# xlr_ingang.net
KiCad netlist of a schematic drawn in Altium Designer
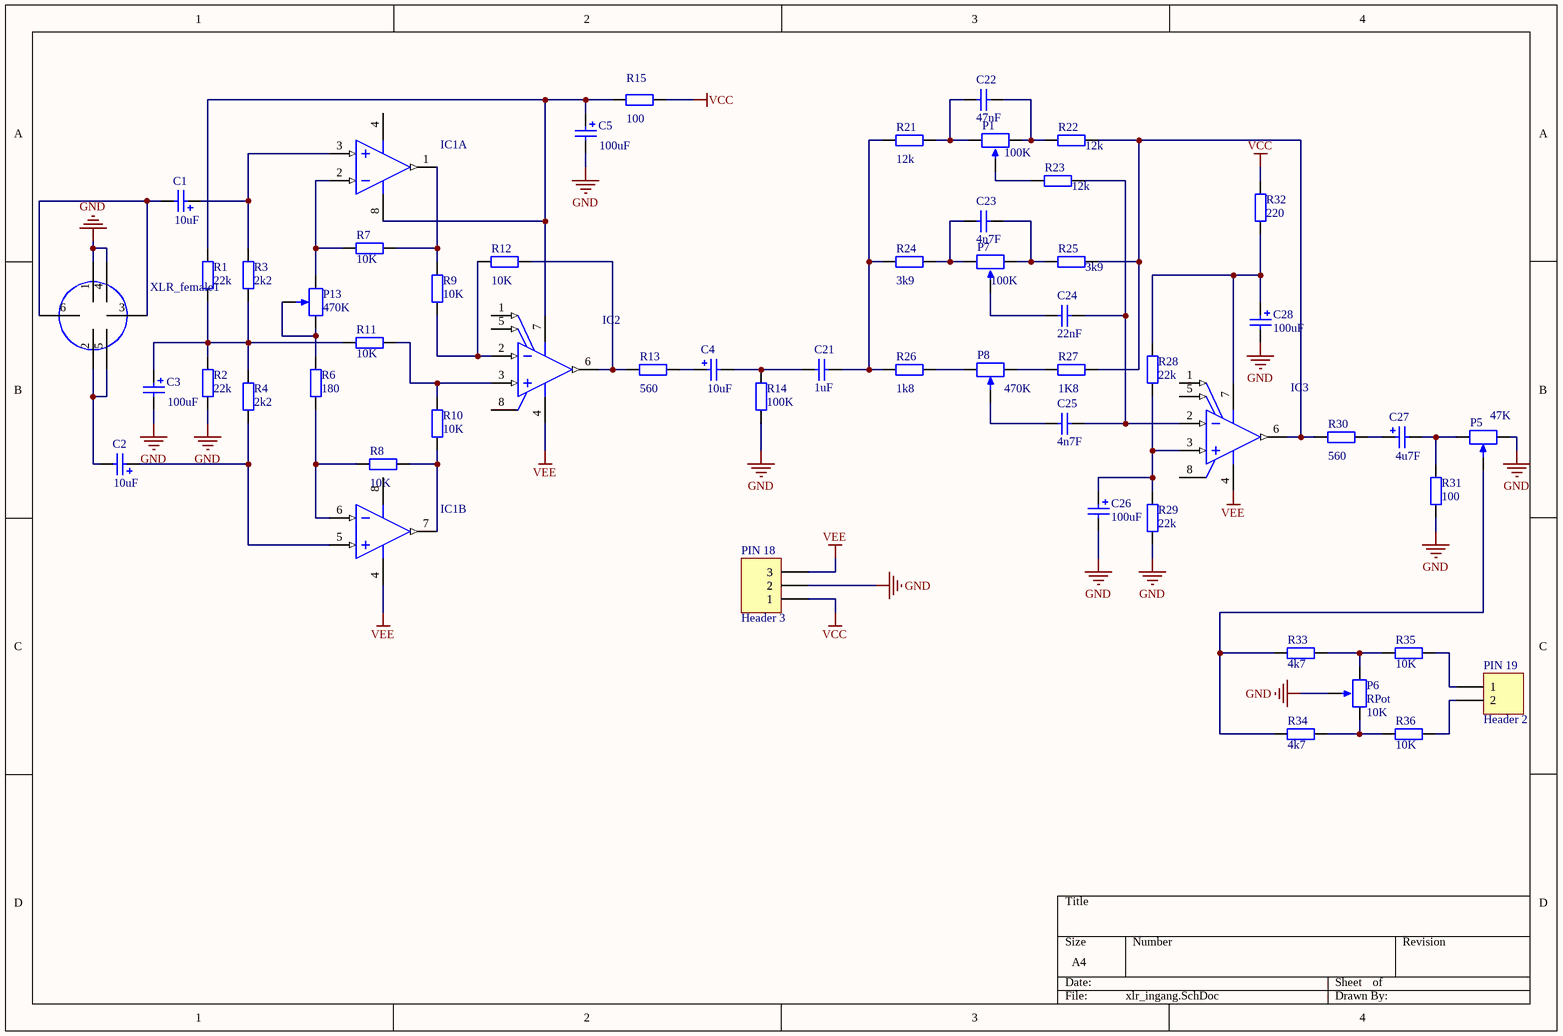
[diagram p0: xlr_ingang.SchDoc]

(export (version "E")
  (design (tool "Eeschema 10.0.6"))
  (components
    (comp (ref "C1")
      (value "10uF")
      (footprint "Capacitor 10uF")
      (description "Polarized Capacitor (Axial)")
      (fields (field (name "Comment") "Cap Pol2") (field (name "PUBLISHER") "Altium Limited"))
      (libsource (lib "Miscellaneous Devices") (part "Cap Pol2"))
    )
    (comp (ref "C2")
      (value "10uF")
      (footprint "Capacitor 10uF")
      (description "Polarized Capacitor (Axial)")
      (fields (field (name "Comment") "Cap Pol2") (field (name "PUBLISHER") "Altium Limited"))
      (libsource (lib "Miscellaneous Devices") (part "Cap Pol2"))
    )
    (comp (ref "C3")
      (value "100uF")
      (footprint "Capacitor 100uF")
      (description "Polarized Capacitor (Axial)")
      (fields (field (name "Comment") "Cap Pol2") (field (name "PUBLISHER") "Altium Limited"))
      (libsource (lib "Miscellaneous Devices") (part "Cap Pol2"))
    )
    (comp (ref "C4")
      (value "10uF")
      (footprint "Capacitor 10uF")
      (description "Polarized Capacitor (Axial)")
      (fields (field (name "Comment") "Cap Pol2") (field (name "PUBLISHER") "Altium Limited"))
      (libsource (lib "Miscellaneous Devices") (part "Cap Pol2"))
    )
    (comp (ref "C5")
      (value "100uF")
      (footprint "Capacitor 100uF")
      (description "Polarized Capacitor (Axial)")
      (fields (field (name "Comment") "Cap Pol2") (field (name "PUBLISHER") "Altium Limited"))
      (libsource (lib "Miscellaneous Devices") (part "Cap Pol2"))
    )
    (comp (ref "C21")
      (value "1uF")
      (footprint "Capacitor 1uF")
      (description "Capacitor")
      (fields (field (name "Comment") "Cap") (field (name "PUBLISHER") "Altium Limited"))
      (libsource (lib "Autio_Mixer") (part "Cap"))
    )
    (comp (ref "C22")
      (value "47nF")
      (footprint "Capacitor 22nF, 47nF, 100nF")
      (description "Capacitor")
      (fields (field (name "Comment") "Cap") (field (name "PUBLISHER") "Altium Limited"))
      (libsource (lib "Autio_Mixer") (part "Cap"))
    )
    (comp (ref "C23")
      (value "4n7F")
      (footprint "Capacitor 22nF, 47nF, 100nF")
      (description "Capacitor")
      (fields (field (name "Comment") "Cap") (field (name "PUBLISHER") "Altium Limited"))
      (libsource (lib "Autio_Mixer") (part "Cap"))
    )
    (comp (ref "C24")
      (value "22nF")
      (footprint "Capacitor 22nF, 47nF, 100nF")
      (description "Capacitor")
      (fields (field (name "Comment") "Cap") (field (name "PUBLISHER") "Altium Limited"))
      (libsource (lib "Autio_Mixer") (part "Cap"))
    )
    (comp (ref "C25")
      (value "4n7F")
      (footprint "Capacitor 22nF, 47nF, 100nF")
      (description "Capacitor")
      (fields (field (name "Comment") "Cap") (field (name "PUBLISHER") "Altium Limited"))
      (libsource (lib "Autio_Mixer") (part "Cap"))
    )
    (comp (ref "C26")
      (value "100uF")
      (footprint "Capacitor 100uF")
      (description "Polarized Capacitor (Axial)")
      (fields (field (name "Comment") "Cap Pol2") (field (name "PUBLISHER") "Altium Limited"))
      (libsource (lib "Miscellaneous Devices") (part "Cap Pol2"))
    )
    (comp (ref "C27")
      (value "4u7F")
      (footprint "Capacitor 4u7F")
      (description "Polarized Capacitor (Axial)")
      (fields (field (name "Comment") "Cap Pol2") (field (name "PUBLISHER") "Altium Limited"))
      (libsource (lib "Miscellaneous Devices") (part "Cap Pol2"))
    )
    (comp (ref "C28")
      (value "100uF")
      (footprint "Capacitor 100uF")
      (description "Polarized Capacitor (Axial)")
      (fields (field (name "Comment") "Cap Pol2") (field (name "PUBLISHER") "Altium Limited"))
      (libsource (lib "Miscellaneous Devices") (part "Cap Pol2"))
    )
    (comp (ref "IC1")
      (value "LM833DR2G")
      (footprint "OPAMP_LM833")
      (description "Low Noise, Audio Dual Operational Amplifier, -40 to 85 degC, 8-Pin SOIC, Pb-Free, Tape and Reel")
      (fields (field (name "MANUFACTURER") "On Semiconductor"))
      (libsource (lib "Autio_Mixer") (part "opamp_LM833"))
    )
    (comp (ref "IC2")
      (value "TL061CD")
      (footprint "OPAMP_TL061")
      (fields (field (name "MANUFACTURER") "Texas Instruments"))
      (libsource (lib "Autio_Mixer") (part "opamp_L061"))
    )
    (comp (ref "IC3")
      (value "TL061CD")
      (footprint "OPAMP_TL061")
      (fields (field (name "MANUFACTURER") "Texas Instruments"))
      (libsource (lib "Autio_Mixer") (part "opamp_TL061"))
    )
    (comp (ref "P1")
      (value "100K")
      (footprint "header_3")
      (description "Potentiometer")
      (fields (field (name "Comment") "RPot") (field (name "PUBLISHER") "Altium Limited"))
      (libsource (lib "") (part "RPot_1"))
    )
    (comp (ref "P5")
      (value "47K")
      (footprint "header_3")
      (description "Potentiometer")
      (fields (field (name "Comment") "RPot") (field (name "PUBLISHER") "Altium Limited"))
      (libsource (lib "Autio_Mixer") (part "RPot_1"))
    )
    (comp (ref "P6")
      (value "RPot")
      (footprint "header_3")
      (description "Potentiometer")
      (fields (field (name "ALTIUM_VALUE") "10K") (field (name "PUBLISHER") "Altium Limited"))
      (libsource (lib "Autio_Mixer") (part "RPot"))
    )
    (comp (ref "P7")
      (value "100K")
      (footprint "header_3")
      (description "Potentiometer")
      (fields (field (name "Comment") "RPot") (field (name "PUBLISHER") "Altium Limited"))
      (libsource (lib "") (part "RPot_1"))
    )
    (comp (ref "P8")
      (value "470K")
      (footprint "header_3")
      (description "Potentiometer")
      (fields (field (name "Comment") "RPot") (field (name "PUBLISHER") "Altium Limited"))
      (libsource (lib "Autio_Mixer") (part "RPot_1"))
    )
    (comp (ref "P13")
      (value "470K")
      (footprint "header_3")
      (description "Potentiometer")
      (fields (field (name "Comment") "RPot") (field (name "PUBLISHER") "Altium Limited"))
      (libsource (lib "") (part "RPot_1_1"))
    )
    (comp (ref "PIN 18")
      (value "Header 3")
      (footprint "header_3")
      (description "Header, 3-Pin")
      (fields (field (name "PUBLISHER") "Altium Limited"))
      (libsource (lib "Miscellaneous Connectors") (part "Header 3"))
    )
    (comp (ref "PIN 19")
      (value "Header 2")
      (footprint "header_2")
      (description "Header, 2-Pin")
      (fields (field (name "PUBLISHER") "Altium Limited"))
      (libsource (lib "Miscellaneous Connectors") (part "Header 2"))
    )
    (comp (ref "R1")
      (value "22k")
      (footprint "C1206")
      (description "Resistor")
      (fields (field (name "Comment") "Res2") (field (name "PUBLISHER") "Altium Limited"))
      (libsource (lib "Miscellaneous Devices") (part "Res2"))
    )
    (comp (ref "R2")
      (value "22k")
      (footprint "C1206")
      (description "Resistor")
      (fields (field (name "Comment") "Res2") (field (name "PUBLISHER") "Altium Limited"))
      (libsource (lib "Miscellaneous Devices") (part "Res2"))
    )
    (comp (ref "R3")
      (value "2k2")
      (footprint "C1206")
      (description "Resistor")
      (fields (field (name "Comment") "Res2") (field (name "PUBLISHER") "Altium Limited"))
      (libsource (lib "Miscellaneous Devices") (part "Res2"))
    )
    (comp (ref "R4")
      (value "2k2")
      (footprint "C1206")
      (description "Resistor")
      (fields (field (name "Comment") "Res2") (field (name "PUBLISHER") "Altium Limited"))
      (libsource (lib "Miscellaneous Devices") (part "Res2"))
    )
    (comp (ref "R6")
      (value "180")
      (footprint "C1206")
      (description "Resistor")
      (fields (field (name "Comment") "Res2") (field (name "PUBLISHER") "Altium Limited"))
      (libsource (lib "Miscellaneous Devices") (part "Res2"))
    )
    (comp (ref "R7")
      (value "10K")
      (footprint "C1206")
      (description "Resistor")
      (fields (field (name "Comment") "Res2") (field (name "PUBLISHER") "Altium Limited"))
      (libsource (lib "") (part "Res2_1"))
    )
    (comp (ref "R8")
      (value "10K")
      (footprint "C1206")
      (description "Resistor")
      (fields (field (name "Comment") "Res2") (field (name "PUBLISHER") "Altium Limited"))
      (libsource (lib "") (part "Res2_1"))
    )
    (comp (ref "R9")
      (value "10K")
      (footprint "C1206")
      (description "Resistor")
      (fields (field (name "Comment") "Res2") (field (name "PUBLISHER") "Altium Limited"))
      (libsource (lib "Miscellaneous Devices") (part "Res2"))
    )
    (comp (ref "R10")
      (value "10K")
      (footprint "C1206")
      (description "Resistor")
      (fields (field (name "Comment") "Res2") (field (name "PUBLISHER") "Altium Limited"))
      (libsource (lib "Miscellaneous Devices") (part "Res2"))
    )
    (comp (ref "R11")
      (value "10K")
      (footprint "C1206")
      (description "Resistor")
      (fields (field (name "Comment") "Res2") (field (name "PUBLISHER") "Altium Limited"))
      (libsource (lib "") (part "Res2_1"))
    )
    (comp (ref "R12")
      (value "10K")
      (footprint "C1206")
      (description "Resistor")
      (fields (field (name "Comment") "Res2") (field (name "PUBLISHER") "Altium Limited"))
      (libsource (lib "") (part "Res2_1"))
    )
    (comp (ref "R13")
      (value "560")
      (footprint "C1206")
      (description "Resistor")
      (fields (field (name "Comment") "Res2") (field (name "PUBLISHER") "Altium Limited"))
      (libsource (lib "") (part "Res2_1"))
    )
    (comp (ref "R14")
      (value "100K")
      (footprint "C1206")
      (description "Resistor")
      (fields (field (name "Comment") "Res2") (field (name "PUBLISHER") "Altium Limited"))
      (libsource (lib "Miscellaneous Devices") (part "Res2"))
    )
    (comp (ref "R15")
      (value "100")
      (footprint "C1206")
      (description "Resistor")
      (fields (field (name "Comment") "Res2") (field (name "PUBLISHER") "Altium Limited"))
      (libsource (lib "") (part "Res2_1"))
    )
    (comp (ref "R21")
      (value "12k")
      (footprint "C1206")
      (description "Resistor")
      (fields (field (name "Comment") "Res2") (field (name "PUBLISHER") "Altium Limited"))
      (libsource (lib "") (part "Res2_1"))
    )
    (comp (ref "R22")
      (value "12k")
      (footprint "C1206")
      (description "Resistor")
      (fields (field (name "Comment") "Res2") (field (name "PUBLISHER") "Altium Limited"))
      (libsource (lib "") (part "Res2_1"))
    )
    (comp (ref "R23")
      (value "12k")
      (footprint "C1206")
      (description "Resistor")
      (fields (field (name "Comment") "Res2") (field (name "PUBLISHER") "Altium Limited"))
      (libsource (lib "") (part "Res2_1"))
    )
    (comp (ref "R24")
      (value "3k9")
      (footprint "C1206")
      (description "Resistor")
      (fields (field (name "Comment") "Res2") (field (name "PUBLISHER") "Altium Limited"))
      (libsource (lib "") (part "Res2_1"))
    )
    (comp (ref "R25")
      (value "3k9")
      (footprint "C1206")
      (description "Resistor")
      (fields (field (name "Comment") "Res2") (field (name "PUBLISHER") "Altium Limited"))
      (libsource (lib "") (part "Res2_1"))
    )
    (comp (ref "R26")
      (value "1k8")
      (footprint "C1206")
      (description "Resistor")
      (fields (field (name "Comment") "Res2") (field (name "PUBLISHER") "Altium Limited"))
      (libsource (lib "") (part "Res2_1"))
    )
    (comp (ref "R27")
      (value "1K8")
      (footprint "C1206")
      (description "Resistor")
      (fields (field (name "Comment") "Res2") (field (name "PUBLISHER") "Altium Limited"))
      (libsource (lib "") (part "Res2_1"))
    )
    (comp (ref "R28")
      (value "22k")
      (footprint "C1206")
      (description "Resistor")
      (fields (field (name "Comment") "Res2") (field (name "PUBLISHER") "Altium Limited"))
      (libsource (lib "Miscellaneous Devices") (part "Res2"))
    )
    (comp (ref "R29")
      (value "22k")
      (footprint "C1206")
      (description "Resistor")
      (fields (field (name "Comment") "Res2") (field (name "PUBLISHER") "Altium Limited"))
      (libsource (lib "Miscellaneous Devices") (part "Res2"))
    )
    (comp (ref "R30")
      (value "560")
      (footprint "C1206")
      (description "Resistor")
      (fields (field (name "Comment") "Res2") (field (name "PUBLISHER") "Altium Limited"))
      (libsource (lib "") (part "Res2_1"))
    )
    (comp (ref "R31")
      (value "100")
      (footprint "C1206")
      (description "Resistor")
      (fields (field (name "Comment") "Res2") (field (name "PUBLISHER") "Altium Limited"))
      (libsource (lib "Miscellaneous Devices") (part "Res2"))
    )
    (comp (ref "R32")
      (value "220")
      (footprint "C1206")
      (description "Resistor")
      (fields (field (name "Comment") "Res2") (field (name "PUBLISHER") "Altium Limited"))
      (libsource (lib "Miscellaneous Devices") (part "Res2"))
    )
    (comp (ref "R33")
      (value "4k7")
      (footprint "C1206")
      (description "Resistor")
      (fields (field (name "Comment") "Res2") (field (name "PUBLISHER") "Altium Limited"))
      (libsource (lib "Autio_Mixer") (part "Res2_13"))
    )
    (comp (ref "R34")
      (value "4k7")
      (footprint "C1206")
      (description "Resistor")
      (fields (field (name "Comment") "Res2") (field (name "PUBLISHER") "Altium Limited"))
      (libsource (lib "Autio_Mixer") (part "Res2_13"))
    )
    (comp (ref "R35")
      (value "10K")
      (footprint "C1206")
      (description "Resistor")
      (fields (field (name "Comment") "Res2") (field (name "PUBLISHER") "Altium Limited"))
      (libsource (lib "Autio_Mixer") (part "Res2_3"))
    )
    (comp (ref "R36")
      (value "10K")
      (footprint "C1206")
      (description "Resistor")
      (fields (field (name "Comment") "Res2") (field (name "PUBLISHER") "Altium Limited"))
      (libsource (lib "Autio_Mixer") (part "Res2_3"))
    )
    (comp (ref "XLR_female1")
      (value "XLR_female")
      (footprint "XLR_Femail_Neutrik_NCJ6FA-V")
      (libsource (lib "Autio_Mixer") (part "XLR_female"))
    )
  )
  (nets
    (net (code "1") (name "GND") (class "Default")
      (node (ref "C26") (pin "2") (pinfunction "2_2") (pintype "passive"))
      (node (ref "C28") (pin "2") (pinfunction "2_2") (pintype "passive"))
      (node (ref "C3") (pin "2") (pinfunction "2_2") (pintype "passive"))
      (node (ref "C5") (pin "2") (pinfunction "2_2") (pintype "passive"))
      (node (ref "P5") (pin "3") (pinfunction "BOT_3") (pintype "passive"))
      (node (ref "P6") (pin "2") (pinfunction "TAP_2") (pintype "passive"))
      (node (ref "PIN 18") (pin "1") (pinfunction "2_1") (pintype "passive"))
      (node (ref "R14") (pin "1") (pinfunction "1_1") (pintype "passive"))
      (node (ref "R2") (pin "1") (pinfunction "1_1") (pintype "passive"))
      (node (ref "R29") (pin "1") (pinfunction "1_1") (pintype "passive"))
      (node (ref "R31") (pin "1") (pinfunction "1_1") (pintype "passive"))
      (node (ref "XLR_female1") (pin "1") (pinfunction "GND_1") (pintype "passive"))
      (node (ref "XLR_female1") (pin "4") (pinfunction "Sleeve_/_GND_4") (pintype "passive"))
    )
    (net (code "2") (name "Net-(C3-Pad1)") (class "Default")
      (node (ref "C3") (pin "1") (pinfunction "1_1") (pintype "passive"))
      (node (ref "R1") (pin "1") (pinfunction "1_1") (pintype "passive"))
      (node (ref "R11") (pin "1") (pinfunction "1_1") (pintype "passive"))
      (node (ref "R2") (pin "2") (pinfunction "2_2") (pintype "passive"))
      (node (ref "R3") (pin "1") (pinfunction "1_1") (pintype "passive"))
      (node (ref "R4") (pin "2") (pinfunction "2_2") (pintype "passive"))
    )
    (net (code "3") (name "Net-(C4-Pad1)") (class "Default")
      (node (ref "C4") (pin "1") (pinfunction "1_1") (pintype "passive"))
      (node (ref "R13") (pin "2") (pinfunction "2_2") (pintype "passive"))
    )
    (net (code "4") (name "Net-(C21-Pad1)") (class "Default")
      (node (ref "C21") (pin "1") (pinfunction "1_1") (pintype "passive"))
      (node (ref "C4") (pin "2") (pinfunction "2_2") (pintype "passive"))
      (node (ref "R14") (pin "2") (pinfunction "2_2") (pintype "passive"))
    )
    (net (code "5") (name "Net-(C21-Pad2)") (class "Default")
      (node (ref "C21") (pin "2") (pinfunction "2_2") (pintype "passive"))
      (node (ref "R21") (pin "1") (pinfunction "1_1") (pintype "passive"))
      (node (ref "R24") (pin "1") (pinfunction "1_1") (pintype "passive"))
      (node (ref "R26") (pin "1") (pinfunction "1_1") (pintype "passive"))
    )
    (net (code "6") (name "Net-(C27-Pad1)") (class "Default")
      (node (ref "C27") (pin "1") (pinfunction "1_1") (pintype "passive"))
      (node (ref "R30") (pin "2") (pinfunction "2_2") (pintype "passive"))
    )
    (net (code "7") (name "Net-(IC1A-IN1+)") (class "Default")
      (node (ref "C1") (pin "1") (pinfunction "1_1") (pintype "passive"))
      (node (ref "IC1") (pin "3") (pinfunction "IN1+_3") (pintype "input"))
      (node (ref "R3") (pin "2") (pinfunction "2_2") (pintype "passive"))
    )
    (net (code "8") (name "Net-(IC1A-IN1-)") (class "Default")
      (node (ref "IC1") (pin "2") (pinfunction "IN1-_2") (pintype "input"))
      (node (ref "P13") (pin "3") (pinfunction "TOP_3") (pintype "passive"))
      (node (ref "R7") (pin "1") (pinfunction "1_1") (pintype "passive"))
    )
    (net (code "9") (name "Net-(IC1A-OUT1)") (class "Default")
      (node (ref "IC1") (pin "1") (pinfunction "OUT1_1") (pintype "output"))
      (node (ref "R7") (pin "2") (pinfunction "2_2") (pintype "passive"))
      (node (ref "R9") (pin "2") (pinfunction "2_2") (pintype "passive"))
    )
    (net (code "10") (name "Net-(IC1A-VCC)") (class "Default")
      (node (ref "C5") (pin "1") (pinfunction "1_1") (pintype "passive"))
      (node (ref "IC1") (pin "8") (pinfunction "VCC_8") (pintype "power_in"))
      (node (ref "IC2") (pin "7") (pinfunction "VCC+_7") (pintype "power_in"))
      (node (ref "R1") (pin "2") (pinfunction "2_2") (pintype "passive"))
      (node (ref "R15") (pin "1") (pinfunction "1_1") (pintype "passive"))
    )
    (net (code "11") (name "Net-(IC1B-IN2+)") (class "Default")
      (node (ref "C2") (pin "1") (pinfunction "1_1") (pintype "passive"))
      (node (ref "IC1") (pin "5") (pinfunction "IN2+_5") (pintype "input"))
      (node (ref "R4") (pin "1") (pinfunction "1_1") (pintype "passive"))
    )
    (net (code "12") (name "Net-(IC1B-IN2-)") (class "Default")
      (node (ref "IC1") (pin "6") (pinfunction "IN2-_6") (pintype "input"))
      (node (ref "R6") (pin "1") (pinfunction "1_1") (pintype "passive"))
      (node (ref "R8") (pin "1") (pinfunction "1_1") (pintype "passive"))
    )
    (net (code "13") (name "Net-(IC1B-OUT2)") (class "Default")
      (node (ref "IC1") (pin "7") (pinfunction "OUT2_7") (pintype "output"))
      (node (ref "R10") (pin "1") (pinfunction "1_1") (pintype "passive"))
      (node (ref "R8") (pin "2") (pinfunction "2_2") (pintype "passive"))
    )
    (net (code "14") (name "Net-(IC2-IN+)") (class "Default")
      (node (ref "IC2") (pin "3") (pinfunction "IN+_3") (pintype "input"))
      (node (ref "R10") (pin "2") (pinfunction "2_2") (pintype "passive"))
      (node (ref "R11") (pin "2") (pinfunction "2_2") (pintype "passive"))
    )
    (net (code "15") (name "Net-(IC2-IN-)") (class "Default")
      (node (ref "IC2") (pin "2") (pinfunction "IN-_2") (pintype "input"))
      (node (ref "R12") (pin "1") (pinfunction "1_1") (pintype "passive"))
      (node (ref "R9") (pin "1") (pinfunction "1_1") (pintype "passive"))
    )
    (net (code "16") (name "Net-(IC2-OUT)") (class "Default")
      (node (ref "IC2") (pin "6") (pinfunction "OUT_6") (pintype "output"))
      (node (ref "R12") (pin "2") (pinfunction "2_2") (pintype "passive"))
      (node (ref "R13") (pin "1") (pinfunction "1_1") (pintype "passive"))
    )
    (net (code "17") (name "Net-(IC3-IN+)") (class "Default")
      (node (ref "C26") (pin "1") (pinfunction "1_1") (pintype "passive"))
      (node (ref "IC3") (pin "3") (pinfunction "IN+_3") (pintype "input"))
      (node (ref "R28") (pin "1") (pinfunction "1_1") (pintype "passive"))
      (node (ref "R29") (pin "2") (pinfunction "2_2") (pintype "passive"))
    )
    (net (code "18") (name "Net-(IC3-IN-)") (class "Default")
      (node (ref "C24") (pin "2") (pinfunction "2_2") (pintype "passive"))
      (node (ref "C25") (pin "2") (pinfunction "2_2") (pintype "passive"))
      (node (ref "IC3") (pin "2") (pinfunction "IN-_2") (pintype "input"))
      (node (ref "R23") (pin "2") (pinfunction "2_2") (pintype "passive"))
    )
    (net (code "19") (name "Net-(IC3-OUT)") (class "Default")
      (node (ref "IC3") (pin "6") (pinfunction "OUT_6") (pintype "output"))
      (node (ref "R22") (pin "2") (pinfunction "2_2") (pintype "passive"))
      (node (ref "R25") (pin "2") (pinfunction "2_2") (pintype "passive"))
      (node (ref "R27") (pin "2") (pinfunction "2_2") (pintype "passive"))
      (node (ref "R30") (pin "1") (pinfunction "1_1") (pintype "passive"))
    )
    (net (code "20") (name "Net-(IC3-VCC+)") (class "Default")
      (node (ref "C28") (pin "1") (pinfunction "1_1") (pintype "passive"))
      (node (ref "IC3") (pin "7") (pinfunction "VCC+_7") (pintype "power_in"))
      (node (ref "R28") (pin "2") (pinfunction "2_2") (pintype "passive"))
      (node (ref "R32") (pin "1") (pinfunction "1_1") (pintype "passive"))
    )
    (net (code "21") (name "Net-(P1-BOT)") (class "Default")
      (node (ref "C22") (pin "2") (pinfunction "2_2") (pintype "passive"))
      (node (ref "P1") (pin "3") (pinfunction "BOT_3") (pintype "passive"))
      (node (ref "R22") (pin "1") (pinfunction "1_1") (pintype "passive"))
    )
    (net (code "22") (name "Net-(P1-TAP)") (class "Default")
      (node (ref "P1") (pin "2") (pinfunction "TAP_2") (pintype "passive"))
      (node (ref "R23") (pin "1") (pinfunction "1_1") (pintype "passive"))
    )
    (net (code "23") (name "Net-(P1-TOP)") (class "Default")
      (node (ref "C22") (pin "1") (pinfunction "1_1") (pintype "passive"))
      (node (ref "P1") (pin "1") (pinfunction "TOP_1") (pintype "passive"))
      (node (ref "R21") (pin "2") (pinfunction "2_2") (pintype "passive"))
    )
    (net (code "24") (name "Net-(P5-TAP)") (class "Default")
      (node (ref "P5") (pin "2") (pinfunction "TAP_2") (pintype "passive"))
      (node (ref "R33") (pin "1") (pinfunction "1_1") (pintype "passive"))
      (node (ref "R34") (pin "1") (pinfunction "1_1") (pintype "passive"))
    )
    (net (code "25") (name "Net-(P5-TOP)") (class "Default")
      (node (ref "C27") (pin "2") (pinfunction "2_2") (pintype "passive"))
      (node (ref "P5") (pin "1") (pinfunction "TOP_1") (pintype "passive"))
      (node (ref "R31") (pin "2") (pinfunction "2_2") (pintype "passive"))
    )
    (net (code "26") (name "Net-(P6-BOT)") (class "Default")
      (node (ref "P6") (pin "3") (pinfunction "BOT_3") (pintype "passive"))
      (node (ref "R34") (pin "2") (pinfunction "2_2") (pintype "passive"))
      (node (ref "R36") (pin "1") (pinfunction "1_1") (pintype "passive"))
    )
    (net (code "27") (name "Net-(P6-TOP)") (class "Default")
      (node (ref "P6") (pin "1") (pinfunction "TOP_1") (pintype "passive"))
      (node (ref "R33") (pin "2") (pinfunction "2_2") (pintype "passive"))
      (node (ref "R35") (pin "1") (pinfunction "1_1") (pintype "passive"))
    )
    (net (code "28") (name "Net-(P7-BOT)") (class "Default")
      (node (ref "C23") (pin "2") (pinfunction "2_2") (pintype "passive"))
      (node (ref "P7") (pin "3") (pinfunction "BOT_3") (pintype "passive"))
      (node (ref "R25") (pin "1") (pinfunction "1_1") (pintype "passive"))
    )
    (net (code "29") (name "Net-(P7-TAP)") (class "Default")
      (node (ref "C24") (pin "1") (pinfunction "1_1") (pintype "passive"))
      (node (ref "P7") (pin "2") (pinfunction "TAP_2") (pintype "passive"))
    )
    (net (code "30") (name "Net-(P7-TOP)") (class "Default")
      (node (ref "C23") (pin "1") (pinfunction "1_1") (pintype "passive"))
      (node (ref "P7") (pin "1") (pinfunction "TOP_1") (pintype "passive"))
      (node (ref "R24") (pin "2") (pinfunction "2_2") (pintype "passive"))
    )
    (net (code "31") (name "Net-(P8-BOT)") (class "Default")
      (node (ref "P8") (pin "3") (pinfunction "BOT_3") (pintype "passive"))
      (node (ref "R27") (pin "1") (pinfunction "1_1") (pintype "passive"))
    )
    (net (code "32") (name "Net-(P8-TAP)") (class "Default")
      (node (ref "C25") (pin "1") (pinfunction "1_1") (pintype "passive"))
      (node (ref "P8") (pin "2") (pinfunction "TAP_2") (pintype "passive"))
    )
    (net (code "33") (name "Net-(P8-TOP)") (class "Default")
      (node (ref "P8") (pin "1") (pinfunction "TOP_1") (pintype "passive"))
      (node (ref "R26") (pin "2") (pinfunction "2_2") (pintype "passive"))
    )
    (net (code "34") (name "Net-(P13-BOT)") (class "Default")
      (node (ref "P13") (pin "1") (pinfunction "TAP_1") (pintype "passive"))
      (node (ref "P13") (pin "2") (pinfunction "BOT_2") (pintype "passive"))
      (node (ref "R6") (pin "2") (pinfunction "2_2") (pintype "passive"))
    )
    (net (code "35") (name "Net-(PIN 19-1)") (class "Default")
      (node (ref "PIN 19") (pin "2") (pinfunction "1_2") (pintype "passive"))
      (node (ref "R35") (pin "2") (pinfunction "2_2") (pintype "passive"))
    )
    (net (code "36") (name "Net-(PIN 19-2)") (class "Default")
      (node (ref "PIN 19") (pin "1") (pinfunction "2_1") (pintype "passive"))
      (node (ref "R36") (pin "2") (pinfunction "2_2") (pintype "passive"))
    )
    (net (code "37") (name "Net-(XLR_female1-Pos)") (class "Default")
      (node (ref "C2") (pin "2") (pinfunction "2_2") (pintype "passive"))
      (node (ref "XLR_female1") (pin "2") (pinfunction "Pos_2") (pintype "passive"))
      (node (ref "XLR_female1") (pin "5") (pinfunction "Ring_/_neg_5") (pintype "passive"))
    )
    (net (code "38") (name "Net-(XLR_female1-Tip_{slash}_pos)") (class "Default")
      (node (ref "C1") (pin "2") (pinfunction "2_2") (pintype "passive"))
      (node (ref "XLR_female1") (pin "3") (pinfunction "negative_3") (pintype "passive"))
      (node (ref "XLR_female1") (pin "6") (pinfunction "Tip_/_pos_6") (pintype "passive"))
    )
    (net (code "39") (name "VCC") (class "Default")
      (node (ref "PIN 18") (pin "2") (pinfunction "1_2") (pintype "passive"))
      (node (ref "R15") (pin "2") (pinfunction "2_2") (pintype "passive"))
      (node (ref "R32") (pin "2") (pinfunction "2_2") (pintype "passive"))
    )
    (net (code "40") (name "VEE") (class "Default")
      (node (ref "IC1") (pin "4") (pinfunction "VEE_4") (pintype "power_in"))
      (node (ref "IC2") (pin "4") (pinfunction "VCC-_4") (pintype "power_in"))
      (node (ref "IC3") (pin "4") (pinfunction "VCC-_4") (pintype "power_in"))
      (node (ref "PIN 18") (pin "3") (pinfunction "3_3") (pintype "passive"))
    )
    (net (code "41") (name "unconnected-(IC1A-VEE-Pad4)") (class "Default")
      (node (ref "IC1") (pin "4") (pinfunction "VEE_4") (pintype "power_in"))
    )
    (net (code "42") (name "unconnected-(IC1B-VCC-Pad8)") (class "Default")
      (node (ref "IC1") (pin "8") (pinfunction "VCC_8") (pintype "power_in"))
    )
    (net (code "43") (name "unconnected-(IC2-NC-Pad8)") (class "Default")
      (node (ref "IC2") (pin "8") (pinfunction "NC_8") (pintype "passive"))
    )
    (net (code "44") (name "unconnected-(IC2-OFFSET_N1-Pad1)") (class "Default")
      (node (ref "IC2") (pin "1") (pinfunction "OFFSET_N1_1") (pintype "input"))
    )
    (net (code "45") (name "unconnected-(IC2-OFFSET_N2-Pad5)") (class "Default")
      (node (ref "IC2") (pin "5") (pinfunction "OFFSET_N2_5") (pintype "input"))
    )
    (net (code "46") (name "unconnected-(IC3-NC-Pad8)") (class "Default")
      (node (ref "IC3") (pin "8") (pinfunction "NC_8") (pintype "passive"))
    )
    (net (code "47") (name "unconnected-(IC3-OFFSET_N1-Pad1)") (class "Default")
      (node (ref "IC3") (pin "1") (pinfunction "OFFSET_N1_1") (pintype "input"))
    )
    (net (code "48") (name "unconnected-(IC3-OFFSET_N2-Pad5)") (class "Default")
      (node (ref "IC3") (pin "5") (pinfunction "OFFSET_N2_5") (pintype "input"))
    )
  )
)
